# frontpanel.net
KiCad netlist of a schematic drawn in EAGLE
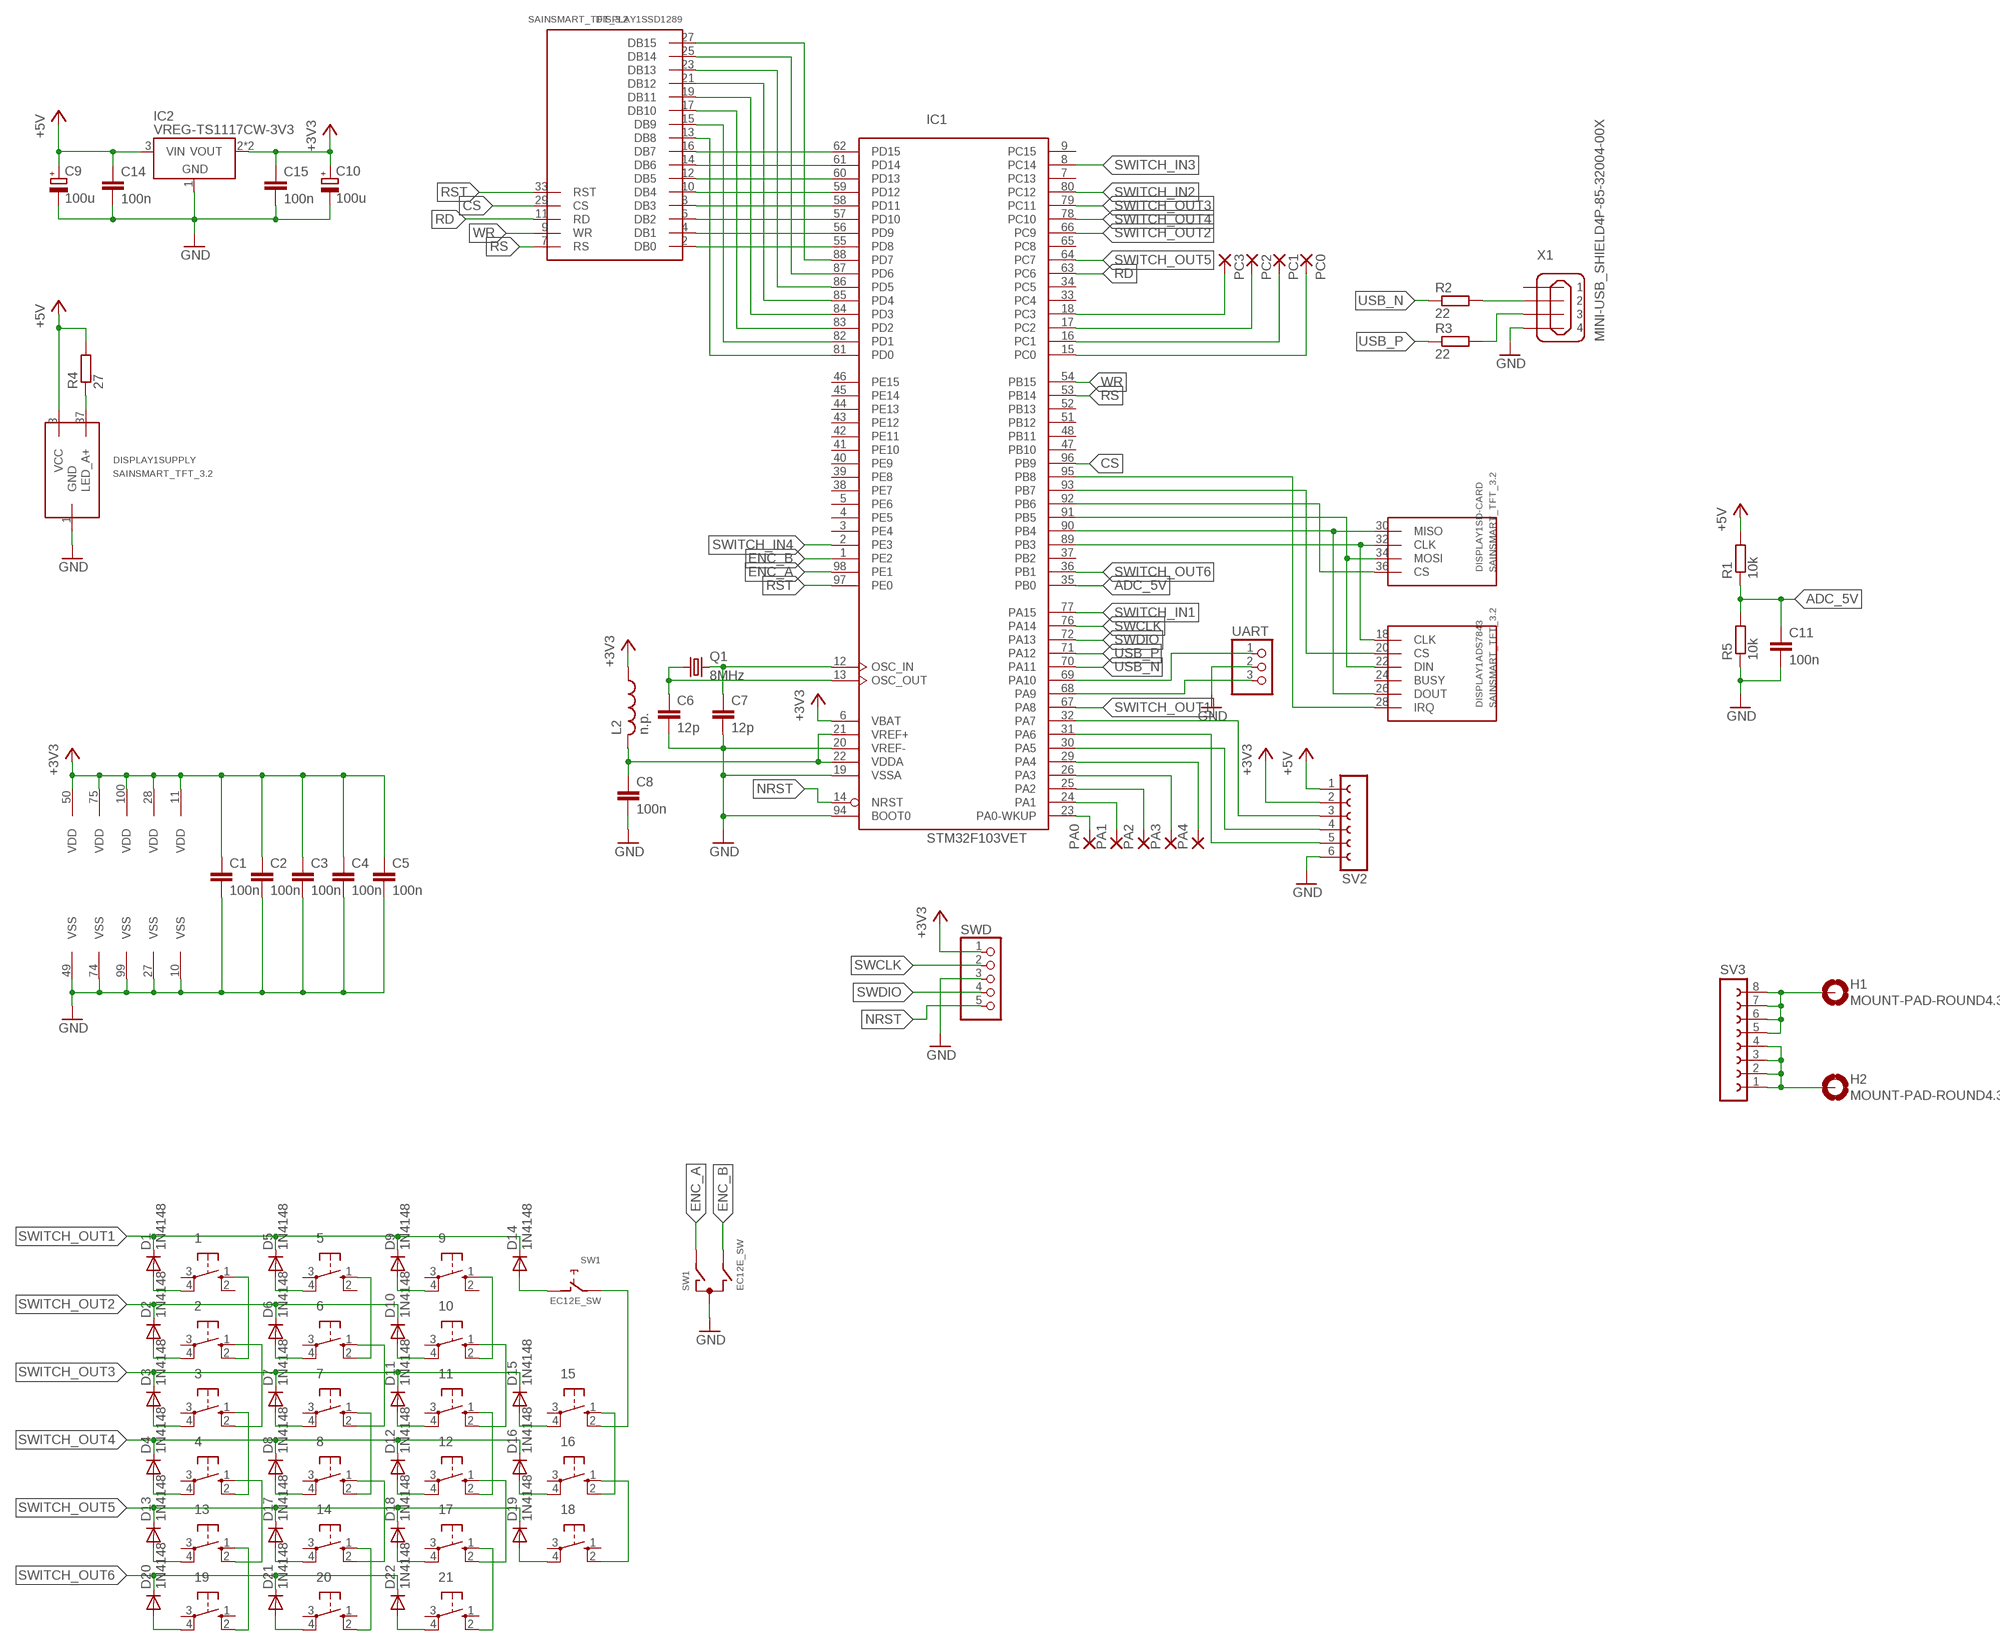
[diagram p0: schematic, sheet 1]

(export (version "E")
  (design (tool "Eeschema 10.0.6"))
  (components
    (comp (ref "1")
      (value "10-XXSMD")
      (footprint "eagle-import:SMD")
      (libsource (lib "eagle-import") (part "10-XXSMD"))
    )
    (comp (ref "2")
      (value "10-XXSMD")
      (footprint "eagle-import:SMD")
      (libsource (lib "eagle-import") (part "10-XXSMD"))
    )
    (comp (ref "3")
      (value "10-XXSMD")
      (footprint "eagle-import:SMD")
      (libsource (lib "eagle-import") (part "10-XXSMD"))
    )
    (comp (ref "4")
      (value "10-XXSMD")
      (footprint "eagle-import:SMD")
      (libsource (lib "eagle-import") (part "10-XXSMD"))
    )
    (comp (ref "5")
      (value "10-XXSMD")
      (footprint "eagle-import:SMD")
      (libsource (lib "eagle-import") (part "10-XXSMD"))
    )
    (comp (ref "6")
      (value "10-XXSMD")
      (footprint "eagle-import:SMD")
      (libsource (lib "eagle-import") (part "10-XXSMD"))
    )
    (comp (ref "7")
      (value "10-XXSMD")
      (footprint "eagle-import:SMD")
      (libsource (lib "eagle-import") (part "10-XXSMD"))
    )
    (comp (ref "8")
      (value "10-XXSMD")
      (footprint "eagle-import:SMD")
      (libsource (lib "eagle-import") (part "10-XXSMD"))
    )
    (comp (ref "9")
      (value "10-XXSMD")
      (footprint "eagle-import:SMD")
      (libsource (lib "eagle-import") (part "10-XXSMD"))
    )
    (comp (ref "10")
      (value "10-XXSMD")
      (footprint "eagle-import:SMD")
      (libsource (lib "eagle-import") (part "10-XXSMD"))
    )
    (comp (ref "11")
      (value "10-XXSMD")
      (footprint "eagle-import:SMD")
      (libsource (lib "eagle-import") (part "10-XXSMD"))
    )
    (comp (ref "12")
      (value "10-XXSMD")
      (footprint "eagle-import:SMD")
      (libsource (lib "eagle-import") (part "10-XXSMD"))
    )
    (comp (ref "13")
      (value "10-XXSMD")
      (footprint "eagle-import:SMD")
      (libsource (lib "eagle-import") (part "10-XXSMD"))
    )
    (comp (ref "14")
      (value "10-XXSMD")
      (footprint "eagle-import:SMD")
      (libsource (lib "eagle-import") (part "10-XXSMD"))
    )
    (comp (ref "15")
      (value "10-XXSMD")
      (footprint "eagle-import:SMD")
      (libsource (lib "eagle-import") (part "10-XXSMD"))
    )
    (comp (ref "16")
      (value "10-XXSMD")
      (footprint "eagle-import:SMD")
      (libsource (lib "eagle-import") (part "10-XXSMD"))
    )
    (comp (ref "17")
      (value "10-XXSMD")
      (footprint "eagle-import:SMD")
      (libsource (lib "eagle-import") (part "10-XXSMD"))
    )
    (comp (ref "18")
      (value "10-XXSMD")
      (footprint "eagle-import:SMD")
      (libsource (lib "eagle-import") (part "10-XXSMD"))
    )
    (comp (ref "19")
      (value "10-XXSMD")
      (footprint "eagle-import:SMD")
      (libsource (lib "eagle-import") (part "10-XXSMD"))
    )
    (comp (ref "20")
      (value "10-XXSMD")
      (footprint "eagle-import:SMD")
      (libsource (lib "eagle-import") (part "10-XXSMD"))
    )
    (comp (ref "21")
      (value "10-XXSMD")
      (footprint "eagle-import:SMD")
      (libsource (lib "eagle-import") (part "10-XXSMD"))
    )
    (comp (ref "C1")
      (value "100n")
      (footprint "eagle-import:C0603K")
      (libsource (lib "eagle-import") (part "C-EUC0603K"))
    )
    (comp (ref "C2")
      (value "100n")
      (footprint "eagle-import:C0603K")
      (libsource (lib "eagle-import") (part "C-EUC0603K"))
    )
    (comp (ref "C3")
      (value "100n")
      (footprint "eagle-import:C0603K")
      (libsource (lib "eagle-import") (part "C-EUC0603K"))
    )
    (comp (ref "C4")
      (value "100n")
      (footprint "eagle-import:C0603K")
      (libsource (lib "eagle-import") (part "C-EUC0603K"))
    )
    (comp (ref "C5")
      (value "100n")
      (footprint "eagle-import:C0603K")
      (libsource (lib "eagle-import") (part "C-EUC0603K"))
    )
    (comp (ref "C6")
      (value "12p")
      (footprint "eagle-import:C0603K")
      (libsource (lib "eagle-import") (part "C-EUC0603K"))
    )
    (comp (ref "C7")
      (value "12p")
      (footprint "eagle-import:C0603K")
      (libsource (lib "eagle-import") (part "C-EUC0603K"))
    )
    (comp (ref "C8")
      (value "100n")
      (footprint "eagle-import:C0603K")
      (libsource (lib "eagle-import") (part "C-EUC0603K"))
    )
    (comp (ref "C9")
      (value "100u")
      (footprint "eagle-import:153CLV-0505")
      (libsource (lib "eagle-import") (part "CPOL-EU153CLV-0505"))
    )
    (comp (ref "C10")
      (value "100u")
      (footprint "eagle-import:153CLV-0505")
      (libsource (lib "eagle-import") (part "CPOL-EU153CLV-0505"))
    )
    (comp (ref "C11")
      (value "100n")
      (footprint "eagle-import:C0603K")
      (libsource (lib "eagle-import") (part "resistormod_C-EUC0603K"))
    )
    (comp (ref "C14")
      (value "100n")
      (footprint "eagle-import:C0603K")
      (libsource (lib "eagle-import") (part "resistormod_C-EUC0603K"))
    )
    (comp (ref "C15")
      (value "100n")
      (footprint "eagle-import:C0603K")
      (libsource (lib "eagle-import") (part "resistormod_C-EUC0603K"))
    )
    (comp (ref "D1")
      (value "1N4148")
      (footprint "eagle-import:SOD323-W")
      (libsource (lib "eagle-import") (part "DIODE-SOD323-W"))
    )
    (comp (ref "D2")
      (value "1N4148")
      (footprint "eagle-import:SOD323-W")
      (libsource (lib "eagle-import") (part "DIODE-SOD323-W"))
    )
    (comp (ref "D3")
      (value "1N4148")
      (footprint "eagle-import:SOD323-W")
      (libsource (lib "eagle-import") (part "DIODE-SOD323-W"))
    )
    (comp (ref "D4")
      (value "1N4148")
      (footprint "eagle-import:SOD323-W")
      (libsource (lib "eagle-import") (part "DIODE-SOD323-W"))
    )
    (comp (ref "D5")
      (value "1N4148")
      (footprint "eagle-import:SOD323-W")
      (libsource (lib "eagle-import") (part "DIODE-SOD323-W"))
    )
    (comp (ref "D6")
      (value "1N4148")
      (footprint "eagle-import:SOD323-W")
      (libsource (lib "eagle-import") (part "DIODE-SOD323-W"))
    )
    (comp (ref "D7")
      (value "1N4148")
      (footprint "eagle-import:SOD323-W")
      (libsource (lib "eagle-import") (part "DIODE-SOD323-W"))
    )
    (comp (ref "D8")
      (value "1N4148")
      (footprint "eagle-import:SOD323-W")
      (libsource (lib "eagle-import") (part "DIODE-SOD323-W"))
    )
    (comp (ref "D9")
      (value "1N4148")
      (footprint "eagle-import:SOD323-W")
      (libsource (lib "eagle-import") (part "DIODE-SOD323-W"))
    )
    (comp (ref "D10")
      (value "1N4148")
      (footprint "eagle-import:SOD323-W")
      (libsource (lib "eagle-import") (part "DIODE-SOD323-W"))
    )
    (comp (ref "D11")
      (value "1N4148")
      (footprint "eagle-import:SOD323-W")
      (libsource (lib "eagle-import") (part "DIODE-SOD323-W"))
    )
    (comp (ref "D12")
      (value "1N4148")
      (footprint "eagle-import:SOD323-W")
      (libsource (lib "eagle-import") (part "DIODE-SOD323-W"))
    )
    (comp (ref "D13")
      (value "1N4148")
      (footprint "eagle-import:SOD323-W")
      (libsource (lib "eagle-import") (part "DIODE-SOD323-W"))
    )
    (comp (ref "D14")
      (value "1N4148")
      (footprint "eagle-import:SOD323-W")
      (libsource (lib "eagle-import") (part "DIODE-SOD323-W"))
    )
    (comp (ref "D15")
      (value "1N4148")
      (footprint "eagle-import:SOD323-W")
      (libsource (lib "eagle-import") (part "DIODE-SOD323-W"))
    )
    (comp (ref "D16")
      (value "1N4148")
      (footprint "eagle-import:SOD323-W")
      (libsource (lib "eagle-import") (part "DIODE-SOD323-W"))
    )
    (comp (ref "D17")
      (value "1N4148")
      (footprint "eagle-import:SOD323-W")
      (libsource (lib "eagle-import") (part "DIODE-SOD323-W"))
    )
    (comp (ref "D18")
      (value "1N4148")
      (footprint "eagle-import:SOD323-W")
      (libsource (lib "eagle-import") (part "DIODE-SOD323-W"))
    )
    (comp (ref "D19")
      (value "1N4148")
      (footprint "eagle-import:SOD323-W")
      (libsource (lib "eagle-import") (part "DIODE-SOD323-W"))
    )
    (comp (ref "D20")
      (value "1N4148")
      (footprint "eagle-import:SOD323-W")
      (libsource (lib "eagle-import") (part "DIODE-SOD323-W"))
    )
    (comp (ref "D21")
      (value "1N4148")
      (footprint "eagle-import:SOD323-W")
      (libsource (lib "eagle-import") (part "DIODE-SOD323-W"))
    )
    (comp (ref "D22")
      (value "1N4148")
      (footprint "eagle-import:SOD323-W")
      (libsource (lib "eagle-import") (part "DIODE-SOD323-W"))
    )
    (comp (ref "DISPLAY1")
      (value "SAINSMART_TFT_3.2")
      (footprint "eagle-import:SAINSMART_TFT_3.2")
      (libsource (lib "eagle-import") (part "SAINSMART_TFT_3.2"))
    )
    (comp (ref "H1")
      (value "MOUNT-PAD-ROUND4.3")
      (footprint "eagle-import:4,3-PAD")
      (libsource (lib "eagle-import") (part "MOUNT-PAD-ROUND4.3"))
    )
    (comp (ref "H2")
      (value "MOUNT-PAD-ROUND4.3")
      (footprint "eagle-import:4,3-PAD")
      (libsource (lib "eagle-import") (part "MOUNT-PAD-ROUND4.3"))
    )
    (comp (ref "IC1")
      (value "STM32F103VET")
      (footprint "eagle-import:LQFP100")
      (libsource (lib "eagle-import") (part "STM32F103VTE"))
    )
    (comp (ref "IC2")
      (value "VREG-TS1117CW-3V3")
      (footprint "eagle-import:SOT223")
      (libsource (lib "eagle-import") (part "VREG-TS1117CW-3V3"))
    )
    (comp (ref "L2")
      (value "n.p.")
      (footprint "eagle-import:R0603")
      (libsource (lib "eagle-import") (part "INDUCTOR0603"))
    )
    (comp (ref "PA0")
      (value "SMD2")
      (footprint "eagle-import:SMD1,27-2,54")
      (libsource (lib "eagle-import") (part "SMD2"))
    )
    (comp (ref "PA1")
      (value "SMD2")
      (footprint "eagle-import:SMD1,27-2,54")
      (libsource (lib "eagle-import") (part "SMD2"))
    )
    (comp (ref "PA2")
      (value "SMD2")
      (footprint "eagle-import:SMD1,27-2,54")
      (libsource (lib "eagle-import") (part "SMD2"))
    )
    (comp (ref "PA3")
      (value "SMD2")
      (footprint "eagle-import:SMD1,27-2,54")
      (libsource (lib "eagle-import") (part "SMD2"))
    )
    (comp (ref "PA4")
      (value "SMD2")
      (footprint "eagle-import:SMD1,27-2,54")
      (libsource (lib "eagle-import") (part "SMD2"))
    )
    (comp (ref "PC0")
      (value "SMD2")
      (footprint "eagle-import:SMD1,27-2,54")
      (libsource (lib "eagle-import") (part "SMD2"))
    )
    (comp (ref "PC1")
      (value "SMD2")
      (footprint "eagle-import:SMD1,27-2,54")
      (libsource (lib "eagle-import") (part "SMD2"))
    )
    (comp (ref "PC2")
      (value "SMD2")
      (footprint "eagle-import:SMD1,27-2,54")
      (libsource (lib "eagle-import") (part "SMD2"))
    )
    (comp (ref "PC3")
      (value "SMD2")
      (footprint "eagle-import:SMD1,27-2,54")
      (libsource (lib "eagle-import") (part "SMD2"))
    )
    (comp (ref "Q1")
      (value "8MHz")
      (footprint "eagle-import:SM49")
      (libsource (lib "eagle-import") (part "CRYSTALSM49"))
    )
    (comp (ref "R1")
      (value "10k")
      (footprint "eagle-import:R0603")
      (libsource (lib "eagle-import") (part "R-EU_R0603"))
    )
    (comp (ref "R2")
      (value "22")
      (footprint "eagle-import:R0603")
      (libsource (lib "eagle-import") (part "R-EU_R0603"))
    )
    (comp (ref "R3")
      (value "22")
      (footprint "eagle-import:R0603")
      (libsource (lib "eagle-import") (part "R-EU_R0603"))
    )
    (comp (ref "R4")
      (value "27")
      (footprint "eagle-import:R1206")
      (libsource (lib "eagle-import") (part "R-EU_R1206"))
    )
    (comp (ref "R5")
      (value "10k")
      (footprint "eagle-import:R0603")
      (libsource (lib "eagle-import") (part "R-EU_R0603"))
    )
    (comp (ref "SV2")
      (value "FE06-1")
      (footprint "eagle-import:FE06")
      (libsource (lib "eagle-import") (part "FE06-1"))
    )
    (comp (ref "SV3")
      (value "FE08-1")
      (footprint "eagle-import:FE08")
      (libsource (lib "eagle-import") (part "FE08-1"))
    )
    (comp (ref "SW1")
      (value "EC12E_SW")
      (footprint "eagle-import:ALPS_EC12E_SW")
      (fields (field (name "MPN") "EC12E2424407"))
      (libsource (lib "eagle-import") (part "EC12E_SW"))
    )
    (comp (ref "SWD")
      (value "PINHD-1X5")
      (footprint "eagle-import:1X05")
      (libsource (lib "eagle-import") (part "PINHD-1X5"))
    )
    (comp (ref "UART")
      (value "PINHD-1X3")
      (footprint "eagle-import:1X03")
      (libsource (lib "eagle-import") (part "PINHD-1X3"))
    )
    (comp (ref "X1")
      (value "MINI-USB_SHIELD4P-85-32004-00X")
      (footprint "eagle-import:85-32004-00X")
      (libsource (lib "eagle-import") (part "MINI-USB_SHIELD4P-85-32004-00X"))
    )
  )
  (nets
    (net (code "1") (name "+3V3") (class "Default")
      (node (ref "C1") (pin "1") (pinfunction "1_1") (pintype "passive"))
      (node (ref "C10") (pin "+") (pinfunction "+_+") (pintype "passive"))
      (node (ref "C15") (pin "1") (pinfunction "1_1") (pintype "passive"))
      (node (ref "C2") (pin "1") (pinfunction "1_1") (pintype "passive"))
      (node (ref "C3") (pin "1") (pinfunction "1_1") (pintype "passive"))
      (node (ref "C4") (pin "1") (pinfunction "1_1") (pintype "passive"))
      (node (ref "C5") (pin "1") (pinfunction "1_1") (pintype "passive"))
      (node (ref "IC1") (pin "100") (pinfunction "VDD_100") (pintype "power_in"))
      (node (ref "IC1") (pin "11") (pinfunction "VDD_11") (pintype "power_in"))
      (node (ref "IC1") (pin "28") (pinfunction "VDD_28") (pintype "power_in"))
      (node (ref "IC1") (pin "50") (pinfunction "VDD_50") (pintype "power_in"))
      (node (ref "IC1") (pin "6") (pinfunction "VBAT_6") (pintype "power_in"))
      (node (ref "IC1") (pin "75") (pinfunction "VDD_75") (pintype "power_in"))
      (node (ref "IC2") (pin "2") (pinfunction "VOUT_2") (pintype "power_in"))
      (node (ref "IC2") (pin "4") (pinfunction "VOUT_4") (pintype "power_in"))
      (node (ref "L2") (pin "1") (pinfunction "1_1") (pintype "passive"))
      (node (ref "SV2") (pin "2") (pinfunction "2_2") (pintype "passive"))
      (node (ref "SWD") (pin "1") (pinfunction "1_1") (pintype "passive"))
    )
    (net (code "2") (name "+5V") (class "Default")
      (node (ref "C14") (pin "1") (pinfunction "1_1") (pintype "passive"))
      (node (ref "C9") (pin "+") (pinfunction "+_+") (pintype "passive"))
      (node (ref "DISPLAY1") (pin "3") (pinfunction "VCC_3") (pintype "bidirectional"))
      (node (ref "IC2") (pin "3") (pinfunction "VIN_3") (pintype "power_in"))
      (node (ref "R1") (pin "2") (pinfunction "2_2") (pintype "passive"))
      (node (ref "R4") (pin "2") (pinfunction "2_2") (pintype "passive"))
      (node (ref "SV2") (pin "1") (pinfunction "1_1") (pintype "passive"))
    )
    (net (code "3") (name "ADC_5V") (class "Default")
      (node (ref "C11") (pin "1") (pinfunction "1_1") (pintype "passive"))
      (node (ref "IC1") (pin "35") (pinfunction "PB0_35") (pintype "bidirectional"))
      (node (ref "R1") (pin "1") (pinfunction "1_1") (pintype "passive"))
      (node (ref "R5") (pin "2") (pinfunction "2_2") (pintype "passive"))
    )
    (net (code "4") (name "CS") (class "Default")
      (node (ref "DISPLAY1") (pin "29") (pinfunction "CS_29") (pintype "bidirectional"))
      (node (ref "IC1") (pin "96") (pinfunction "PB9_96") (pintype "bidirectional"))
    )
    (net (code "5") (name "ENC_A") (class "Default")
      (node (ref "IC1") (pin "98") (pinfunction "PE1_98") (pintype "bidirectional"))
      (node (ref "SW1") (pin "A") (pinfunction "A_A") (pintype "passive"))
    )
    (net (code "6") (name "ENC_B") (class "Default")
      (node (ref "IC1") (pin "1") (pinfunction "PE2_1") (pintype "bidirectional"))
      (node (ref "SW1") (pin "B") (pinfunction "B_B") (pintype "passive"))
    )
    (net (code "7") (name "GND") (class "Default")
      (node (ref "C1") (pin "2") (pinfunction "2_2") (pintype "passive"))
      (node (ref "C10") (pin "-") (pinfunction "-_-") (pintype "passive"))
      (node (ref "C11") (pin "2") (pinfunction "2_2") (pintype "passive"))
      (node (ref "C14") (pin "2") (pinfunction "2_2") (pintype "passive"))
      (node (ref "C15") (pin "2") (pinfunction "2_2") (pintype "passive"))
      (node (ref "C2") (pin "2") (pinfunction "2_2") (pintype "passive"))
      (node (ref "C3") (pin "2") (pinfunction "2_2") (pintype "passive"))
      (node (ref "C4") (pin "2") (pinfunction "2_2") (pintype "passive"))
      (node (ref "C5") (pin "2") (pinfunction "2_2") (pintype "passive"))
      (node (ref "C6") (pin "2") (pinfunction "2_2") (pintype "passive"))
      (node (ref "C7") (pin "2") (pinfunction "2_2") (pintype "passive"))
      (node (ref "C8") (pin "2") (pinfunction "2_2") (pintype "passive"))
      (node (ref "C9") (pin "-") (pinfunction "-_-") (pintype "passive"))
      (node (ref "DISPLAY1") (pin "1") (pinfunction "GND_1") (pintype "bidirectional"))
      (node (ref "IC1") (pin "10") (pinfunction "VSS_10") (pintype "power_in"))
      (node (ref "IC1") (pin "19") (pinfunction "VSSA_19") (pintype "power_in"))
      (node (ref "IC1") (pin "20") (pinfunction "VREF-_20") (pintype "power_in"))
      (node (ref "IC1") (pin "27") (pinfunction "VSS_27") (pintype "power_in"))
      (node (ref "IC1") (pin "49") (pinfunction "VSS_49") (pintype "power_in"))
      (node (ref "IC1") (pin "74") (pinfunction "VSS_74") (pintype "power_in"))
      (node (ref "IC1") (pin "94") (pinfunction "BOOT0_94") (pintype "input"))
      (node (ref "IC1") (pin "99") (pinfunction "VSS_99") (pintype "power_in"))
      (node (ref "IC2") (pin "1") (pinfunction "GND_1") (pintype "power_in"))
      (node (ref "R5") (pin "1") (pinfunction "1_1") (pintype "passive"))
      (node (ref "SV2") (pin "6") (pinfunction "6_6") (pintype "passive"))
      (node (ref "SW1") (pin "C") (pinfunction "C_C") (pintype "passive"))
      (node (ref "SWD") (pin "3") (pinfunction "3_3") (pintype "passive"))
      (node (ref "UART") (pin "2") (pinfunction "2_2") (pintype "passive"))
      (node (ref "X1") (pin "4") (pinfunction "4_4") (pintype "passive"))
    )
    (net (code "8") (name "NRST") (class "Default")
      (node (ref "IC1") (pin "14") (pinfunction "NRST_14") (pintype "bidirectional"))
      (node (ref "SWD") (pin "5") (pinfunction "5_5") (pintype "passive"))
    )
    (net (code "9") (name "Net-(1-P1)") (class "Default")
      (node (ref "1") (pin "4") (pinfunction "P1_4") (pintype "passive"))
      (node (ref "D1") (pin "A") (pinfunction "A_A") (pintype "passive"))
    )
    (net (code "10") (name "Net-(1-S)") (class "Default")
      (node (ref "1") (pin "1") (pinfunction "S_1") (pintype "passive"))
      (node (ref "2") (pin "2") (pinfunction "S1_2") (pintype "passive"))
    )
    (net (code "11") (name "Net-(2-P1)") (class "Default")
      (node (ref "2") (pin "4") (pinfunction "P1_4") (pintype "passive"))
      (node (ref "D2") (pin "A") (pinfunction "A_A") (pintype "passive"))
    )
    (net (code "12") (name "Net-(2-S)") (class "Default")
      (node (ref "2") (pin "1") (pinfunction "S_1") (pintype "passive"))
      (node (ref "3") (pin "2") (pinfunction "S1_2") (pintype "passive"))
    )
    (net (code "13") (name "Net-(3-P1)") (class "Default")
      (node (ref "3") (pin "4") (pinfunction "P1_4") (pintype "passive"))
      (node (ref "D3") (pin "A") (pinfunction "A_A") (pintype "passive"))
    )
    (net (code "14") (name "Net-(4-P1)") (class "Default")
      (node (ref "4") (pin "4") (pinfunction "P1_4") (pintype "passive"))
      (node (ref "D4") (pin "A") (pinfunction "A_A") (pintype "passive"))
    )
    (net (code "15") (name "Net-(5-P1)") (class "Default")
      (node (ref "5") (pin "4") (pinfunction "P1_4") (pintype "passive"))
      (node (ref "D5") (pin "A") (pinfunction "A_A") (pintype "passive"))
    )
    (net (code "16") (name "Net-(5-S)") (class "Default")
      (node (ref "5") (pin "1") (pinfunction "S_1") (pintype "passive"))
      (node (ref "6") (pin "2") (pinfunction "S1_2") (pintype "passive"))
    )
    (net (code "17") (name "Net-(6-P1)") (class "Default")
      (node (ref "6") (pin "4") (pinfunction "P1_4") (pintype "passive"))
      (node (ref "D6") (pin "A") (pinfunction "A_A") (pintype "passive"))
    )
    (net (code "18") (name "Net-(6-S)") (class "Default")
      (node (ref "6") (pin "1") (pinfunction "S_1") (pintype "passive"))
      (node (ref "7") (pin "2") (pinfunction "S1_2") (pintype "passive"))
    )
    (net (code "19") (name "Net-(7-P1)") (class "Default")
      (node (ref "7") (pin "4") (pinfunction "P1_4") (pintype "passive"))
      (node (ref "D7") (pin "A") (pinfunction "A_A") (pintype "passive"))
    )
    (net (code "20") (name "Net-(8-P1)") (class "Default")
      (node (ref "8") (pin "4") (pinfunction "P1_4") (pintype "passive"))
      (node (ref "D8") (pin "A") (pinfunction "A_A") (pintype "passive"))
    )
    (net (code "21") (name "Net-(9-P1)") (class "Default")
      (node (ref "9") (pin "4") (pinfunction "P1_4") (pintype "passive"))
      (node (ref "D9") (pin "A") (pinfunction "A_A") (pintype "passive"))
    )
    (net (code "22") (name "Net-(10-P1)") (class "Default")
      (node (ref "10") (pin "4") (pinfunction "P1_4") (pintype "passive"))
      (node (ref "D10") (pin "A") (pinfunction "A_A") (pintype "passive"))
    )
    (net (code "23") (name "Net-(10-S)") (class "Default")
      (node (ref "10") (pin "1") (pinfunction "S_1") (pintype "passive"))
      (node (ref "11") (pin "2") (pinfunction "S1_2") (pintype "passive"))
    )
    (net (code "24") (name "Net-(10-S1)") (class "Default")
      (node (ref "10") (pin "2") (pinfunction "S1_2") (pintype "passive"))
      (node (ref "9") (pin "1") (pinfunction "S_1") (pintype "passive"))
    )
    (net (code "25") (name "Net-(11-P1)") (class "Default")
      (node (ref "11") (pin "4") (pinfunction "P1_4") (pintype "passive"))
      (node (ref "D11") (pin "A") (pinfunction "A_A") (pintype "passive"))
    )
    (net (code "26") (name "Net-(11-S)") (class "Default")
      (node (ref "11") (pin "1") (pinfunction "S_1") (pintype "passive"))
      (node (ref "12") (pin "2") (pinfunction "S1_2") (pintype "passive"))
    )
    (net (code "27") (name "Net-(12-P1)") (class "Default")
      (node (ref "12") (pin "4") (pinfunction "P1_4") (pintype "passive"))
      (node (ref "D12") (pin "A") (pinfunction "A_A") (pintype "passive"))
    )
    (net (code "28") (name "Net-(13-P1)") (class "Default")
      (node (ref "13") (pin "4") (pinfunction "P1_4") (pintype "passive"))
      (node (ref "D13") (pin "A") (pinfunction "A_A") (pintype "passive"))
    )
    (net (code "29") (name "Net-(13-S)") (class "Default")
      (node (ref "13") (pin "1") (pinfunction "S_1") (pintype "passive"))
      (node (ref "19") (pin "2") (pinfunction "S1_2") (pintype "passive"))
    )
    (net (code "30") (name "Net-(13-S1)") (class "Default")
      (node (ref "13") (pin "2") (pinfunction "S1_2") (pintype "passive"))
      (node (ref "4") (pin "1") (pinfunction "S_1") (pintype "passive"))
    )
    (net (code "31") (name "Net-(14-P1)") (class "Default")
      (node (ref "14") (pin "4") (pinfunction "P1_4") (pintype "passive"))
      (node (ref "D17") (pin "A") (pinfunction "A_A") (pintype "passive"))
    )
    (net (code "32") (name "Net-(14-S)") (class "Default")
      (node (ref "14") (pin "1") (pinfunction "S_1") (pintype "passive"))
      (node (ref "20") (pin "2") (pinfunction "S1_2") (pintype "passive"))
    )
    (net (code "33") (name "Net-(14-S1)") (class "Default")
      (node (ref "14") (pin "2") (pinfunction "S1_2") (pintype "passive"))
      (node (ref "8") (pin "1") (pinfunction "S_1") (pintype "passive"))
    )
    (net (code "34") (name "Net-(15-P1)") (class "Default")
      (node (ref "15") (pin "4") (pinfunction "P1_4") (pintype "passive"))
      (node (ref "D15") (pin "A") (pinfunction "A_A") (pintype "passive"))
    )
    (net (code "35") (name "Net-(15-S)") (class "Default")
      (node (ref "15") (pin "1") (pinfunction "S_1") (pintype "passive"))
      (node (ref "16") (pin "2") (pinfunction "S1_2") (pintype "passive"))
    )
    (net (code "36") (name "Net-(15-S1)") (class "Default")
      (node (ref "15") (pin "2") (pinfunction "S1_2") (pintype "passive"))
      (node (ref "SW1") (pin "E") (pinfunction "2_E") (pintype "passive"))
    )
    (net (code "37") (name "Net-(16-P1)") (class "Default")
      (node (ref "16") (pin "4") (pinfunction "P1_4") (pintype "passive"))
      (node (ref "D16") (pin "A") (pinfunction "A_A") (pintype "passive"))
    )
    (net (code "38") (name "Net-(17-P1)") (class "Default")
      (node (ref "17") (pin "4") (pinfunction "P1_4") (pintype "passive"))
      (node (ref "D18") (pin "A") (pinfunction "A_A") (pintype "passive"))
    )
    (net (code "39") (name "Net-(17-S)") (class "Default")
      (node (ref "17") (pin "1") (pinfunction "S_1") (pintype "passive"))
      (node (ref "21") (pin "2") (pinfunction "S1_2") (pintype "passive"))
    )
    (net (code "40") (name "Net-(18-P1)") (class "Default")
      (node (ref "18") (pin "4") (pinfunction "P1_4") (pintype "passive"))
      (node (ref "D19") (pin "A") (pinfunction "A_A") (pintype "passive"))
    )
    (net (code "41") (name "Net-(19-P1)") (class "Default")
      (node (ref "19") (pin "4") (pinfunction "P1_4") (pintype "passive"))
      (node (ref "D20") (pin "A") (pinfunction "A_A") (pintype "passive"))
    )
    (net (code "42") (name "Net-(20-P1)") (class "Default")
      (node (ref "20") (pin "4") (pinfunction "P1_4") (pintype "passive"))
      (node (ref "D21") (pin "A") (pinfunction "A_A") (pintype "passive"))
    )
    (net (code "43") (name "Net-(21-P1)") (class "Default")
      (node (ref "21") (pin "4") (pinfunction "P1_4") (pintype "passive"))
      (node (ref "D22") (pin "A") (pinfunction "A_A") (pintype "passive"))
    )
    (net (code "44") (name "Net-(DISPLAY1A-CLK)") (class "Default")
      (node (ref "DISPLAY1") (pin "18") (pinfunction "CLK_18") (pintype "bidirectional"))
      (node (ref "DISPLAY1") (pin "32") (pinfunction "CLK_32") (pintype "bidirectional"))
      (node (ref "IC1") (pin "89") (pinfunction "PB3_89") (pintype "bidirectional"))
    )
    (net (code "45") (name "Net-(DISPLAY1A-CS)") (class "Default")
      (node (ref "DISPLAY1") (pin "20") (pinfunction "CS_20") (pintype "bidirectional"))
      (node (ref "IC1") (pin "93") (pinfunction "PB7_93") (pintype "bidirectional"))
    )
    (net (code "46") (name "Net-(DISPLAY1A-DIN)") (class "Default")
      (node (ref "DISPLAY1") (pin "22") (pinfunction "DIN_22") (pintype "bidirectional"))
      (node (ref "DISPLAY1") (pin "34") (pinfunction "MOSI_34") (pintype "bidirectional"))
      (node (ref "IC1") (pin "91") (pinfunction "PB5_91") (pintype "bidirectional"))
    )
    (net (code "47") (name "Net-(DISPLAY1A-DOUT)") (class "Default")
      (node (ref "DISPLAY1") (pin "26") (pinfunction "DOUT_26") (pintype "bidirectional"))
      (node (ref "DISPLAY1") (pin "30") (pinfunction "MISO_30") (pintype "bidirectional"))
      (node (ref "IC1") (pin "90") (pinfunction "PB4_90") (pintype "bidirectional"))
    )
    (net (code "48") (name "Net-(DISPLAY1A-IRQ)") (class "Default")
      (node (ref "DISPLAY1") (pin "28") (pinfunction "IRQ_28") (pintype "bidirectional"))
      (node (ref "IC1") (pin "95") (pinfunction "PB8_95") (pintype "bidirectional"))
    )
    (net (code "49") (name "Net-(DISPLAY1B-CS)") (class "Default")
      (node (ref "DISPLAY1") (pin "36") (pinfunction "CS_36") (pintype "bidirectional"))
      (node (ref "IC1") (pin "92") (pinfunction "PB6_92") (pintype "bidirectional"))
    )
    (net (code "50") (name "Net-(DISPLAY1C-DB0)") (class "Default")
      (node (ref "DISPLAY1") (pin "2") (pinfunction "DB0_2") (pintype "bidirectional"))
      (node (ref "IC1") (pin "55") (pinfunction "PD8_55") (pintype "bidirectional"))
    )
    (net (code "51") (name "Net-(DISPLAY1C-DB1)") (class "Default")
      (node (ref "DISPLAY1") (pin "4") (pinfunction "DB1_4") (pintype "bidirectional"))
      (node (ref "IC1") (pin "56") (pinfunction "PD9_56") (pintype "bidirectional"))
    )
    (net (code "52") (name "Net-(DISPLAY1C-DB2)") (class "Default")
      (node (ref "DISPLAY1") (pin "6") (pinfunction "DB2_6") (pintype "bidirectional"))
      (node (ref "IC1") (pin "57") (pinfunction "PD10_57") (pintype "bidirectional"))
    )
    (net (code "53") (name "Net-(DISPLAY1C-DB3)") (class "Default")
      (node (ref "DISPLAY1") (pin "8") (pinfunction "DB3_8") (pintype "bidirectional"))
      (node (ref "IC1") (pin "58") (pinfunction "PD11_58") (pintype "bidirectional"))
    )
    (net (code "54") (name "Net-(DISPLAY1C-DB4)") (class "Default")
      (node (ref "DISPLAY1") (pin "10") (pinfunction "DB4_10") (pintype "bidirectional"))
      (node (ref "IC1") (pin "59") (pinfunction "PD12_59") (pintype "bidirectional"))
    )
    (net (code "55") (name "Net-(DISPLAY1C-DB5)") (class "Default")
      (node (ref "DISPLAY1") (pin "12") (pinfunction "DB5_12") (pintype "bidirectional"))
      (node (ref "IC1") (pin "60") (pinfunction "PD13_60") (pintype "bidirectional"))
    )
    (net (code "56") (name "Net-(DISPLAY1C-DB6)") (class "Default")
      (node (ref "DISPLAY1") (pin "14") (pinfunction "DB6_14") (pintype "bidirectional"))
      (node (ref "IC1") (pin "61") (pinfunction "PD14_61") (pintype "bidirectional"))
    )
    (net (code "57") (name "Net-(DISPLAY1C-DB7)") (class "Default")
      (node (ref "DISPLAY1") (pin "16") (pinfunction "DB7_16") (pintype "bidirectional"))
      (node (ref "IC1") (pin "62") (pinfunction "PD15_62") (pintype "bidirectional"))
    )
    (net (code "58") (name "Net-(DISPLAY1C-DB8)") (class "Default")
      (node (ref "DISPLAY1") (pin "13") (pinfunction "DB8_13") (pintype "bidirectional"))
      (node (ref "IC1") (pin "81") (pinfunction "PD0_81") (pintype "bidirectional"))
    )
    (net (code "59") (name "Net-(DISPLAY1C-DB9)") (class "Default")
      (node (ref "DISPLAY1") (pin "15") (pinfunction "DB9_15") (pintype "bidirectional"))
      (node (ref "IC1") (pin "82") (pinfunction "PD1_82") (pintype "bidirectional"))
    )
    (net (code "60") (name "Net-(DISPLAY1C-DB10)") (class "Default")
      (node (ref "DISPLAY1") (pin "17") (pinfunction "DB10_17") (pintype "bidirectional"))
      (node (ref "IC1") (pin "83") (pinfunction "PD2_83") (pintype "bidirectional"))
    )
    (net (code "61") (name "Net-(DISPLAY1C-DB11)") (class "Default")
      (node (ref "DISPLAY1") (pin "19") (pinfunction "DB11_19") (pintype "bidirectional"))
      (node (ref "IC1") (pin "84") (pinfunction "PD3_84") (pintype "bidirectional"))
    )
    (net (code "62") (name "Net-(DISPLAY1C-DB12)") (class "Default")
      (node (ref "DISPLAY1") (pin "21") (pinfunction "DB12_21") (pintype "bidirectional"))
      (node (ref "IC1") (pin "85") (pinfunction "PD4_85") (pintype "bidirectional"))
    )
    (net (code "63") (name "Net-(DISPLAY1C-DB13)") (class "Default")
      (node (ref "DISPLAY1") (pin "23") (pinfunction "DB13_23") (pintype "bidirectional"))
      (node (ref "IC1") (pin "86") (pinfunction "PD5_86") (pintype "bidirectional"))
    )
    (net (code "64") (name "Net-(DISPLAY1C-DB14)") (class "Default")
      (node (ref "DISPLAY1") (pin "25") (pinfunction "DB14_25") (pintype "bidirectional"))
      (node (ref "IC1") (pin "87") (pinfunction "PD6_87") (pintype "bidirectional"))
    )
    (net (code "65") (name "Net-(DISPLAY1C-DB15)") (class "Default")
      (node (ref "DISPLAY1") (pin "27") (pinfunction "DB15_27") (pintype "bidirectional"))
      (node (ref "IC1") (pin "88") (pinfunction "PD7_88") (pintype "bidirectional"))
    )
    (net (code "66") (name "Net-(DISPLAY1D-LED_A+)") (class "Default")
      (node (ref "DISPLAY1") (pin "37") (pinfunction "LED_A+_37") (pintype "bidirectional"))
      (node (ref "R4") (pin "1") (pinfunction "1_1") (pintype "passive"))
    )
    (net (code "67") (name "Net-(H1-MOUNT)") (class "Default")
      (node (ref "H1") (pin "B4,3") (pinfunction "MOUNT_B4,3") (pintype "passive"))
      (node (ref "SV3") (pin "5") (pinfunction "5_5") (pintype "passive"))
      (node (ref "SV3") (pin "6") (pinfunction "6_6") (pintype "passive"))
      (node (ref "SV3") (pin "7") (pinfunction "7_7") (pintype "passive"))
      (node (ref "SV3") (pin "8") (pinfunction "8_8") (pintype "passive"))
    )
    (net (code "68") (name "Net-(H2-MOUNT)") (class "Default")
      (node (ref "H2") (pin "B4,3") (pinfunction "MOUNT_B4,3") (pintype "passive"))
      (node (ref "SV3") (pin "1") (pinfunction "1_1") (pintype "passive"))
      (node (ref "SV3") (pin "2") (pinfunction "2_2") (pintype "passive"))
      (node (ref "SV3") (pin "3") (pinfunction "3_3") (pintype "passive"))
      (node (ref "SV3") (pin "4") (pinfunction "4_4") (pintype "passive"))
    )
    (net (code "69") (name "Net-(IC1A-OSC_IN)") (class "Default")
      (node (ref "C7") (pin "1") (pinfunction "1_1") (pintype "passive"))
      (node (ref "IC1") (pin "12") (pinfunction "OSC_IN_12") (pintype "bidirectional"))
      (node (ref "Q1") (pin "2") (pinfunction "2_2") (pintype "passive"))
    )
    (net (code "70") (name "Net-(IC1A-OSC_OUT)") (class "Default")
      (node (ref "C6") (pin "1") (pinfunction "1_1") (pintype "passive"))
      (node (ref "IC1") (pin "13") (pinfunction "OSC_OUT_13") (pintype "bidirectional"))
      (node (ref "Q1") (pin "1") (pinfunction "1_1") (pintype "passive"))
    )
    (net (code "71") (name "Net-(IC1A-PA0-WKUP)") (class "Default")
      (node (ref "IC1") (pin "23") (pinfunction "PA0-WKUP_23") (pintype "bidirectional"))
      (node (ref "PA0") (pin "1") (pinfunction "P_1") (pintype "passive"))
    )
    (net (code "72") (name "Net-(IC1A-PA1)") (class "Default")
      (node (ref "IC1") (pin "24") (pinfunction "PA1_24") (pintype "bidirectional"))
      (node (ref "PA1") (pin "1") (pinfunction "P_1") (pintype "passive"))
    )
    (net (code "73") (name "Net-(IC1A-PA2)") (class "Default")
      (node (ref "IC1") (pin "25") (pinfunction "PA2_25") (pintype "bidirectional"))
      (node (ref "PA2") (pin "1") (pinfunction "P_1") (pintype "passive"))
    )
    (net (code "74") (name "Net-(IC1A-PA3)") (class "Default")
      (node (ref "IC1") (pin "26") (pinfunction "PA3_26") (pintype "bidirectional"))
      (node (ref "PA3") (pin "1") (pinfunction "P_1") (pintype "passive"))
    )
    (net (code "75") (name "Net-(IC1A-PA4)") (class "Default")
      (node (ref "IC1") (pin "29") (pinfunction "PA4_29") (pintype "bidirectional"))
      (node (ref "PA4") (pin "1") (pinfunction "P_1") (pintype "passive"))
    )
    (net (code "76") (name "Net-(IC1A-PA5)") (class "Default")
      (node (ref "IC1") (pin "30") (pinfunction "PA5_30") (pintype "bidirectional"))
      (node (ref "SV2") (pin "4") (pinfunction "4_4") (pintype "passive"))
    )
    (net (code "77") (name "Net-(IC1A-PA6)") (class "Default")
      (node (ref "IC1") (pin "31") (pinfunction "PA6_31") (pintype "bidirectional"))
      (node (ref "SV2") (pin "5") (pinfunction "5_5") (pintype "passive"))
    )
    (net (code "78") (name "Net-(IC1A-PA7)") (class "Default")
      (node (ref "IC1") (pin "32") (pinfunction "PA7_32") (pintype "bidirectional"))
      (node (ref "SV2") (pin "3") (pinfunction "3_3") (pintype "passive"))
    )
    (net (code "79") (name "Net-(IC1A-PA9)") (class "Default")
      (node (ref "IC1") (pin "68") (pinfunction "PA9_68") (pintype "bidirectional"))
      (node (ref "UART") (pin "3") (pinfunction "3_3") (pintype "passive"))
    )
    (net (code "80") (name "Net-(IC1A-PA10)") (class "Default")
      (node (ref "IC1") (pin "69") (pinfunction "PA10_69") (pintype "bidirectional"))
      (node (ref "UART") (pin "1") (pinfunction "1_1") (pintype "passive"))
    )
    (net (code "81") (name "Net-(IC1A-PC0)") (class "Default")
      (node (ref "IC1") (pin "15") (pinfunction "PC0_15") (pintype "bidirectional"))
      (node (ref "PC0") (pin "1") (pinfunction "P_1") (pintype "passive"))
    )
    (net (code "82") (name "Net-(IC1A-PC1)") (class "Default")
      (node (ref "IC1") (pin "16") (pinfunction "PC1_16") (pintype "bidirectional"))
      (node (ref "PC1") (pin "1") (pinfunction "P_1") (pintype "passive"))
    )
    (net (code "83") (name "Net-(IC1A-PC2)") (class "Default")
      (node (ref "IC1") (pin "17") (pinfunction "PC2_17") (pintype "bidirectional"))
      (node (ref "PC2") (pin "1") (pinfunction "P_1") (pintype "passive"))
    )
    (net (code "84") (name "Net-(IC1A-PC3)") (class "Default")
      (node (ref "IC1") (pin "18") (pinfunction "PC3_18") (pintype "bidirectional"))
      (node (ref "PC3") (pin "1") (pinfunction "P_1") (pintype "passive"))
    )
    (net (code "85") (name "Net-(IC1A-VDDA)") (class "Default")
      (node (ref "C8") (pin "1") (pinfunction "1_1") (pintype "passive"))
      (node (ref "IC1") (pin "21") (pinfunction "VREF+_21") (pintype "power_in"))
      (node (ref "IC1") (pin "22") (pinfunction "VDDA_22") (pintype "power_in"))
      (node (ref "L2") (pin "2") (pinfunction "2_2") (pintype "passive"))
    )
    (net (code "86") (name "Net-(R2-Pad2)") (class "Default")
      (node (ref "R2") (pin "2") (pinfunction "2_2") (pintype "passive"))
      (node (ref "X1") (pin "2") (pinfunction "2_2") (pintype "passive"))
    )
    (net (code "87") (name "Net-(R3-Pad2)") (class "Default")
      (node (ref "R3") (pin "2") (pinfunction "2_2") (pintype "passive"))
      (node (ref "X1") (pin "3") (pinfunction "3_3") (pintype "passive"))
    )
    (net (code "88") (name "Net-(SW1B-1)") (class "Default")
      (node (ref "D14") (pin "A") (pinfunction "A_A") (pintype "passive"))
      (node (ref "SW1") (pin "D") (pinfunction "1_D") (pintype "passive"))
    )
    (net (code "89") (name "RD") (class "Default")
      (node (ref "DISPLAY1") (pin "11") (pinfunction "RD_11") (pintype "bidirectional"))
      (node (ref "IC1") (pin "63") (pinfunction "PC6_63") (pintype "bidirectional"))
    )
    (net (code "90") (name "RS") (class "Default")
      (node (ref "DISPLAY1") (pin "7") (pinfunction "RS_7") (pintype "bidirectional"))
      (node (ref "IC1") (pin "53") (pinfunction "PB14_53") (pintype "bidirectional"))
    )
    (net (code "91") (name "RST") (class "Default")
      (node (ref "DISPLAY1") (pin "33") (pinfunction "RST_33") (pintype "bidirectional"))
      (node (ref "IC1") (pin "97") (pinfunction "PE0_97") (pintype "bidirectional"))
    )
    (net (code "92") (name "SWCLK") (class "Default")
      (node (ref "IC1") (pin "76") (pinfunction "PA14_76") (pintype "bidirectional"))
      (node (ref "SWD") (pin "2") (pinfunction "2_2") (pintype "passive"))
    )
    (net (code "93") (name "SWDIO") (class "Default")
      (node (ref "IC1") (pin "72") (pinfunction "PA13_72") (pintype "bidirectional"))
      (node (ref "SWD") (pin "4") (pinfunction "4_4") (pintype "passive"))
    )
    (net (code "94") (name "SWITCH_IN1") (class "Default")
      (node (ref "3") (pin "1") (pinfunction "S_1") (pintype "passive"))
      (node (ref "4") (pin "2") (pinfunction "S1_2") (pintype "passive"))
      (node (ref "IC1") (pin "77") (pinfunction "PA15_77") (pintype "bidirectional"))
    )
    (net (code "95") (name "SWITCH_IN2") (class "Default")
      (node (ref "7") (pin "1") (pinfunction "S_1") (pintype "passive"))
      (node (ref "8") (pin "2") (pinfunction "S1_2") (pintype "passive"))
      (node (ref "IC1") (pin "80") (pinfunction "PC12_80") (pintype "bidirectional"))
    )
    (net (code "96") (name "SWITCH_IN3") (class "Default")
      (node (ref "12") (pin "1") (pinfunction "S_1") (pintype "passive"))
      (node (ref "17") (pin "2") (pinfunction "S1_2") (pintype "passive"))
      (node (ref "IC1") (pin "8") (pinfunction "PC14_8") (pintype "bidirectional"))
    )
    (net (code "97") (name "SWITCH_IN4") (class "Default")
      (node (ref "16") (pin "1") (pinfunction "S_1") (pintype "passive"))
      (node (ref "18") (pin "2") (pinfunction "S1_2") (pintype "passive"))
      (node (ref "IC1") (pin "2") (pinfunction "PE3_2") (pintype "bidirectional"))
    )
    (net (code "98") (name "SWITCH_OUT1") (class "Default")
      (node (ref "D1") (pin "C") (pinfunction "C_C") (pintype "passive"))
      (node (ref "D14") (pin "C") (pinfunction "C_C") (pintype "passive"))
      (node (ref "D5") (pin "C") (pinfunction "C_C") (pintype "passive"))
      (node (ref "D9") (pin "C") (pinfunction "C_C") (pintype "passive"))
      (node (ref "IC1") (pin "67") (pinfunction "PA8_67") (pintype "bidirectional"))
    )
    (net (code "99") (name "SWITCH_OUT2") (class "Default")
      (node (ref "D10") (pin "C") (pinfunction "C_C") (pintype "passive"))
      (node (ref "D2") (pin "C") (pinfunction "C_C") (pintype "passive"))
      (node (ref "D6") (pin "C") (pinfunction "C_C") (pintype "passive"))
      (node (ref "IC1") (pin "66") (pinfunction "PC9_66") (pintype "bidirectional"))
    )
    (net (code "100") (name "SWITCH_OUT3") (class "Default")
      (node (ref "D11") (pin "C") (pinfunction "C_C") (pintype "passive"))
      (node (ref "D15") (pin "C") (pinfunction "C_C") (pintype "passive"))
      (node (ref "D3") (pin "C") (pinfunction "C_C") (pintype "passive"))
      (node (ref "D7") (pin "C") (pinfunction "C_C") (pintype "passive"))
      (node (ref "IC1") (pin "79") (pinfunction "PC11_79") (pintype "bidirectional"))
    )
    (net (code "101") (name "SWITCH_OUT4") (class "Default")
      (node (ref "D12") (pin "C") (pinfunction "C_C") (pintype "passive"))
      (node (ref "D16") (pin "C") (pinfunction "C_C") (pintype "passive"))
      (node (ref "D4") (pin "C") (pinfunction "C_C") (pintype "passive"))
      (node (ref "D8") (pin "C") (pinfunction "C_C") (pintype "passive"))
      (node (ref "IC1") (pin "78") (pinfunction "PC10_78") (pintype "bidirectional"))
    )
    (net (code "102") (name "SWITCH_OUT5") (class "Default")
      (node (ref "D13") (pin "C") (pinfunction "C_C") (pintype "passive"))
      (node (ref "D17") (pin "C") (pinfunction "C_C") (pintype "passive"))
      (node (ref "D18") (pin "C") (pinfunction "C_C") (pintype "passive"))
      (node (ref "D19") (pin "C") (pinfunction "C_C") (pintype "passive"))
      (node (ref "IC1") (pin "64") (pinfunction "PC7_64") (pintype "bidirectional"))
    )
    (net (code "103") (name "SWITCH_OUT6") (class "Default")
      (node (ref "D20") (pin "C") (pinfunction "C_C") (pintype "passive"))
      (node (ref "D21") (pin "C") (pinfunction "C_C") (pintype "passive"))
      (node (ref "D22") (pin "C") (pinfunction "C_C") (pintype "passive"))
      (node (ref "IC1") (pin "36") (pinfunction "PB1_36") (pintype "bidirectional"))
    )
    (net (code "104") (name "USB_N") (class "Default")
      (node (ref "IC1") (pin "70") (pinfunction "PA11_70") (pintype "bidirectional"))
      (node (ref "R2") (pin "1") (pinfunction "1_1") (pintype "passive"))
    )
    (net (code "105") (name "USB_P") (class "Default")
      (node (ref "IC1") (pin "71") (pinfunction "PA12_71") (pintype "bidirectional"))
      (node (ref "R3") (pin "1") (pinfunction "1_1") (pintype "passive"))
    )
    (net (code "106") (name "WR") (class "Default")
      (node (ref "DISPLAY1") (pin "9") (pinfunction "WR_9") (pintype "bidirectional"))
      (node (ref "IC1") (pin "54") (pinfunction "PB15_54") (pintype "bidirectional"))
    )
    (net (code "107") (name "unconnected-(1-P-Pad3)") (class "Default")
      (node (ref "1") (pin "3") (pinfunction "P_3") (pintype "passive"))
    )
    (net (code "108") (name "unconnected-(1-S1-Pad2)") (class "Default")
      (node (ref "1") (pin "2") (pinfunction "S1_2") (pintype "passive"))
    )
    (net (code "109") (name "unconnected-(2-P-Pad3)") (class "Default")
      (node (ref "2") (pin "3") (pinfunction "P_3") (pintype "passive"))
    )
    (net (code "110") (name "unconnected-(3-P-Pad3)") (class "Default")
      (node (ref "3") (pin "3") (pinfunction "P_3") (pintype "passive"))
    )
    (net (code "111") (name "unconnected-(4-P-Pad3)") (class "Default")
      (node (ref "4") (pin "3") (pinfunction "P_3") (pintype "passive"))
    )
    (net (code "112") (name "unconnected-(5-P-Pad3)") (class "Default")
      (node (ref "5") (pin "3") (pinfunction "P_3") (pintype "passive"))
    )
    (net (code "113") (name "unconnected-(5-S1-Pad2)") (class "Default")
      (node (ref "5") (pin "2") (pinfunction "S1_2") (pintype "passive"))
    )
    (net (code "114") (name "unconnected-(6-P-Pad3)") (class "Default")
      (node (ref "6") (pin "3") (pinfunction "P_3") (pintype "passive"))
    )
    (net (code "115") (name "unconnected-(7-P-Pad3)") (class "Default")
      (node (ref "7") (pin "3") (pinfunction "P_3") (pintype "passive"))
    )
    (net (code "116") (name "unconnected-(8-P-Pad3)") (class "Default")
      (node (ref "8") (pin "3") (pinfunction "P_3") (pintype "passive"))
    )
    (net (code "117") (name "unconnected-(9-P-Pad3)") (class "Default")
      (node (ref "9") (pin "3") (pinfunction "P_3") (pintype "passive"))
    )
    (net (code "118") (name "unconnected-(9-S1-Pad2)") (class "Default")
      (node (ref "9") (pin "2") (pinfunction "S1_2") (pintype "passive"))
    )
    (net (code "119") (name "unconnected-(10-P-Pad3)") (class "Default")
      (node (ref "10") (pin "3") (pinfunction "P_3") (pintype "passive"))
    )
    (net (code "120") (name "unconnected-(11-P-Pad3)") (class "Default")
      (node (ref "11") (pin "3") (pinfunction "P_3") (pintype "passive"))
    )
    (net (code "121") (name "unconnected-(12-P-Pad3)") (class "Default")
      (node (ref "12") (pin "3") (pinfunction "P_3") (pintype "passive"))
    )
    (net (code "122") (name "unconnected-(13-P-Pad3)") (class "Default")
      (node (ref "13") (pin "3") (pinfunction "P_3") (pintype "passive"))
    )
    (net (code "123") (name "unconnected-(14-P-Pad3)") (class "Default")
      (node (ref "14") (pin "3") (pinfunction "P_3") (pintype "passive"))
    )
    (net (code "124") (name "unconnected-(15-P-Pad3)") (class "Default")
      (node (ref "15") (pin "3") (pinfunction "P_3") (pintype "passive"))
    )
    (net (code "125") (name "unconnected-(16-P-Pad3)") (class "Default")
      (node (ref "16") (pin "3") (pinfunction "P_3") (pintype "passive"))
    )
    (net (code "126") (name "unconnected-(17-P-Pad3)") (class "Default")
      (node (ref "17") (pin "3") (pinfunction "P_3") (pintype "passive"))
    )
    (net (code "127") (name "unconnected-(18-P-Pad3)") (class "Default")
      (node (ref "18") (pin "3") (pinfunction "P_3") (pintype "passive"))
    )
    (net (code "128") (name "unconnected-(18-S-Pad1)") (class "Default")
      (node (ref "18") (pin "1") (pinfunction "S_1") (pintype "passive"))
    )
    (net (code "129") (name "unconnected-(19-P-Pad3)") (class "Default")
      (node (ref "19") (pin "3") (pinfunction "P_3") (pintype "passive"))
    )
    (net (code "130") (name "unconnected-(19-S-Pad1)") (class "Default")
      (node (ref "19") (pin "1") (pinfunction "S_1") (pintype "passive"))
    )
    (net (code "131") (name "unconnected-(20-P-Pad3)") (class "Default")
      (node (ref "20") (pin "3") (pinfunction "P_3") (pintype "passive"))
    )
    (net (code "132") (name "unconnected-(20-S-Pad1)") (class "Default")
      (node (ref "20") (pin "1") (pinfunction "S_1") (pintype "passive"))
    )
    (net (code "133") (name "unconnected-(21-P-Pad3)") (class "Default")
      (node (ref "21") (pin "3") (pinfunction "P_3") (pintype "passive"))
    )
    (net (code "134") (name "unconnected-(21-S-Pad1)") (class "Default")
      (node (ref "21") (pin "1") (pinfunction "S_1") (pintype "passive"))
    )
    (net (code "135") (name "unconnected-(DISPLAY1A-BUSY-Pad24)") (class "Default")
      (node (ref "DISPLAY1") (pin "24") (pinfunction "BUSY_24") (pintype "bidirectional"))
    )
    (net (code "136") (name "unconnected-(IC1A-PB2-Pad37)") (class "Default")
      (node (ref "IC1") (pin "37") (pinfunction "PB2_37") (pintype "bidirectional"))
    )
    (net (code "137") (name "unconnected-(IC1A-PB10-Pad47)") (class "Default")
      (node (ref "IC1") (pin "47") (pinfunction "PB10_47") (pintype "bidirectional"))
    )
    (net (code "138") (name "unconnected-(IC1A-PB11-Pad48)") (class "Default")
      (node (ref "IC1") (pin "48") (pinfunction "PB11_48") (pintype "bidirectional"))
    )
    (net (code "139") (name "unconnected-(IC1A-PB12-Pad51)") (class "Default")
      (node (ref "IC1") (pin "51") (pinfunction "PB12_51") (pintype "bidirectional"))
    )
    (net (code "140") (name "unconnected-(IC1A-PB13-Pad52)") (class "Default")
      (node (ref "IC1") (pin "52") (pinfunction "PB13_52") (pintype "bidirectional"))
    )
    (net (code "141") (name "unconnected-(IC1A-PC4-Pad33)") (class "Default")
      (node (ref "IC1") (pin "33") (pinfunction "PC4_33") (pintype "bidirectional"))
    )
    (net (code "142") (name "unconnected-(IC1A-PC5-Pad34)") (class "Default")
      (node (ref "IC1") (pin "34") (pinfunction "PC5_34") (pintype "bidirectional"))
    )
    (net (code "143") (name "unconnected-(IC1A-PC8-Pad65)") (class "Default")
      (node (ref "IC1") (pin "65") (pinfunction "PC8_65") (pintype "bidirectional"))
    )
    (net (code "144") (name "unconnected-(IC1A-PC13-Pad7)") (class "Default")
      (node (ref "IC1") (pin "7") (pinfunction "PC13_7") (pintype "bidirectional"))
    )
    (net (code "145") (name "unconnected-(IC1A-PC15-Pad9)") (class "Default")
      (node (ref "IC1") (pin "9") (pinfunction "PC15_9") (pintype "bidirectional"))
    )
    (net (code "146") (name "unconnected-(IC1A-PE4-Pad3)") (class "Default")
      (node (ref "IC1") (pin "3") (pinfunction "PE4_3") (pintype "bidirectional"))
    )
    (net (code "147") (name "unconnected-(IC1A-PE5-Pad4)") (class "Default")
      (node (ref "IC1") (pin "4") (pinfunction "PE5_4") (pintype "bidirectional"))
    )
    (net (code "148") (name "unconnected-(IC1A-PE6-Pad5)") (class "Default")
      (node (ref "IC1") (pin "5") (pinfunction "PE6_5") (pintype "bidirectional"))
    )
    (net (code "149") (name "unconnected-(IC1A-PE7-Pad38)") (class "Default")
      (node (ref "IC1") (pin "38") (pinfunction "PE7_38") (pintype "bidirectional"))
    )
    (net (code "150") (name "unconnected-(IC1A-PE8-Pad39)") (class "Default")
      (node (ref "IC1") (pin "39") (pinfunction "PE8_39") (pintype "bidirectional"))
    )
    (net (code "151") (name "unconnected-(IC1A-PE9-Pad40)") (class "Default")
      (node (ref "IC1") (pin "40") (pinfunction "PE9_40") (pintype "bidirectional"))
    )
    (net (code "152") (name "unconnected-(IC1A-PE10-Pad41)") (class "Default")
      (node (ref "IC1") (pin "41") (pinfunction "PE10_41") (pintype "bidirectional"))
    )
    (net (code "153") (name "unconnected-(IC1A-PE11-Pad42)") (class "Default")
      (node (ref "IC1") (pin "42") (pinfunction "PE11_42") (pintype "bidirectional"))
    )
    (net (code "154") (name "unconnected-(IC1A-PE12-Pad43)") (class "Default")
      (node (ref "IC1") (pin "43") (pinfunction "PE12_43") (pintype "bidirectional"))
    )
    (net (code "155") (name "unconnected-(IC1A-PE13-Pad44)") (class "Default")
      (node (ref "IC1") (pin "44") (pinfunction "PE13_44") (pintype "bidirectional"))
    )
    (net (code "156") (name "unconnected-(IC1A-PE14-Pad45)") (class "Default")
      (node (ref "IC1") (pin "45") (pinfunction "PE14_45") (pintype "bidirectional"))
    )
    (net (code "157") (name "unconnected-(IC1A-PE15-Pad46)") (class "Default")
      (node (ref "IC1") (pin "46") (pinfunction "PE15_46") (pintype "bidirectional"))
    )
    (net (code "158") (name "unconnected-(X1-Pad1)") (class "Default")
      (node (ref "X1") (pin "1") (pinfunction "1_1") (pintype "passive"))
    )
  )
)
